# LED_Controller_Board.net
KiCad netlist of a schematic drawn in EAGLE
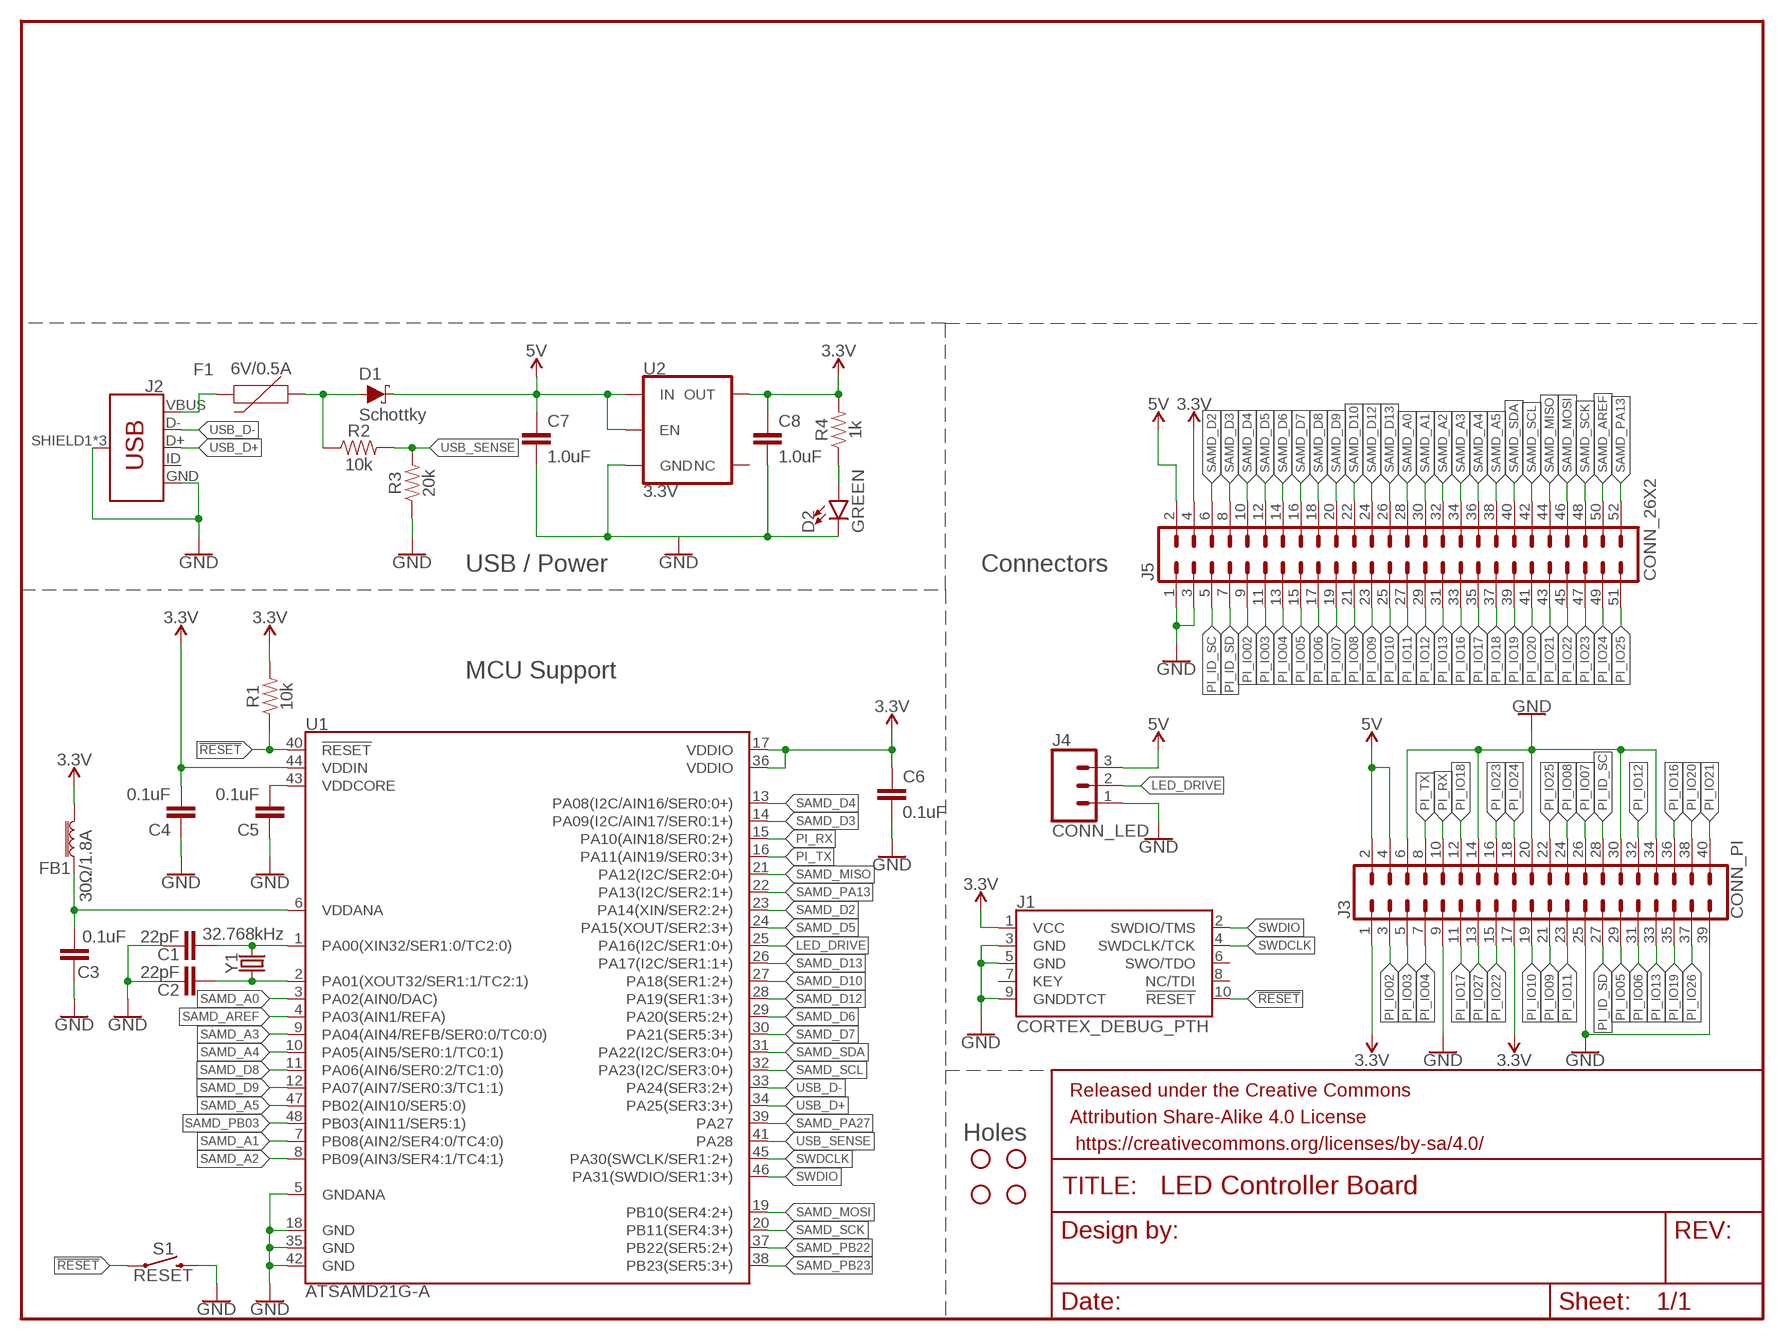
[diagram p0: schematic, sheet 1]

(export (version "E")
  (design (tool "Eeschema 10.0.6"))
  (components
    (comp (ref "C1")
      (value "22pF")
      (footprint "eagle-import:0603")
      (libsource (lib "eagle-import") (part "22PF-0603-50V-5%"))
    )
    (comp (ref "C2")
      (value "22pF")
      (footprint "eagle-import:0603")
      (libsource (lib "eagle-import") (part "22PF-0603-50V-5%"))
    )
    (comp (ref "C3")
      (value "0.1uF")
      (footprint "eagle-import:0603")
      (libsource (lib "eagle-import") (part "0.1UF-0603-25V-5%"))
    )
    (comp (ref "C4")
      (value "0.1uF")
      (footprint "eagle-import:0603")
      (libsource (lib "eagle-import") (part "0.1UF-0603-25V-5%"))
    )
    (comp (ref "C5")
      (value "0.1uF")
      (footprint "eagle-import:0603")
      (libsource (lib "eagle-import") (part "0.1UF-0603-25V-5%"))
    )
    (comp (ref "C6")
      (value "0.1uF")
      (footprint "eagle-import:0603")
      (libsource (lib "eagle-import") (part "0.1UF-0603-25V-5%"))
    )
    (comp (ref "C7")
      (value "1.0uF")
      (footprint "eagle-import:0603")
      (libsource (lib "eagle-import") (part "1.0UF-0603-16V-10%"))
    )
    (comp (ref "C8")
      (value "1.0uF")
      (footprint "eagle-import:0603")
      (libsource (lib "eagle-import") (part "1.0UF-0603-16V-10%"))
    )
    (comp (ref "D1")
      (value "Schottky")
      (footprint "eagle-import:SOD-323")
      (libsource (lib "eagle-import") (part "DIODE-SCHOTTKY-BAT20J"))
    )
    (comp (ref "D2")
      (value "GREEN")
      (footprint "eagle-import:LED-0603")
      (libsource (lib "eagle-import") (part "LED-GREEN0603"))
    )
    (comp (ref "F1")
      (value "6V/0.5A")
      (footprint "eagle-import:1206")
      (libsource (lib "eagle-import") (part "PPTC_HALF-AMP"))
    )
    (comp (ref "FB1")
      (value "30Ω/1.8A")
      (footprint "eagle-import:0603")
      (libsource (lib "eagle-import") (part "FERRITE_BEAD-0603"))
    )
    (comp (ref "FRAME1")
      (value "FRAME-LETTERNO_PACKAGE")
      (footprint "eagle-import:DUMMY")
      (fields (field (name "DESIGNER") "Nobody"))
      (libsource (lib "eagle-import") (part "FRAME-LETTERNO_PACKAGE"))
    )
    (comp (ref "H1")
      (value "STAND-OFFTIGHT")
      (footprint "eagle-import:STAND-OFF-TIGHT")
      (libsource (lib "eagle-import") (part "STAND-OFFTIGHT"))
    )
    (comp (ref "H2")
      (value "STAND-OFFTIGHT")
      (footprint "eagle-import:STAND-OFF-TIGHT")
      (libsource (lib "eagle-import") (part "STAND-OFFTIGHT"))
    )
    (comp (ref "H3")
      (value "STAND-OFFTIGHT")
      (footprint "eagle-import:STAND-OFF-TIGHT")
      (libsource (lib "eagle-import") (part "STAND-OFFTIGHT"))
    )
    (comp (ref "H4")
      (value "STAND-OFFTIGHT")
      (footprint "eagle-import:STAND-OFF-TIGHT")
      (libsource (lib "eagle-import") (part "STAND-OFFTIGHT"))
    )
    (comp (ref "J1")
      (value "CORTEX_DEBUG_PTH")
      (footprint "eagle-import:2X5-PTH-1.27MM")
      (libsource (lib "eagle-import") (part "CORTEX_DEBUG_PTH"))
    )
    (comp (ref "J2")
      (value "USB_MICRO-B_FEMALE-SMT")
      (footprint "eagle-import:USB-B-MICRO-SMD")
      (libsource (lib "eagle-import") (part "USB_MICRO-B_FEMALE-SMT"))
    )
    (comp (ref "J3")
      (value "CONN_PI")
      (footprint "eagle-import:2X20")
      (libsource (lib "eagle-import") (part "CONN_20X2"))
    )
    (comp (ref "J4")
      (value "CONN_LED")
      (footprint "eagle-import:1X03_LOCK")
      (libsource (lib "eagle-import") (part "CONN_03LOCK"))
    )
    (comp (ref "J5")
      (value "CONN_26X2")
      (footprint "eagle-import:2X26")
      (libsource (lib "eagle-import") (part "CONN_26X2"))
    )
    (comp (ref "R1")
      (value "10k")
      (footprint "eagle-import:0603")
      (libsource (lib "eagle-import") (part "10KOHM-0603-1/10W-1%"))
    )
    (comp (ref "R2")
      (value "10k")
      (footprint "eagle-import:0603")
      (libsource (lib "eagle-import") (part "10KOHM-0603-1/10W-1%"))
    )
    (comp (ref "R3")
      (value "20k")
      (footprint "eagle-import:0603")
      (libsource (lib "eagle-import") (part "20KOHM-0603-1/10W-1%"))
    )
    (comp (ref "R4")
      (value "1k")
      (footprint "eagle-import:0603")
      (libsource (lib "eagle-import") (part "1KOHM-0603-1/10W-1%"))
    )
    (comp (ref "S1")
      (value "RESET")
      (footprint "eagle-import:TACTILE_SWITCH_PTH_RIGHT_ANGLE_KIT")
      (libsource (lib "eagle-import") (part "MOMENTARY-SWITCH-SPST-PTH-RIGHT-ANGLE-KIT"))
    )
    (comp (ref "U1")
      (value "ATSAMD21G-A")
      (footprint "eagle-import:TQFP-48")
      (libsource (lib "eagle-import") (part "ATSAMD21G-A"))
    )
    (comp (ref "U2")
      (value "3.3V")
      (footprint "eagle-import:SOT23-5")
      (libsource (lib "eagle-import") (part "V_REG_AP2112K-3.3V"))
    )
    (comp (ref "Y1")
      (value "32.768kHz")
      (footprint "eagle-import:CRYSTAL-SMD-3.2X1.5MM")
      (libsource (lib "eagle-import") (part "CRYSTAL-32.768KHZSMD-3.2X1.5"))
    )
  )
  (nets
    (net (code "1") (name "/~{RESET}") (class "Default")
      (node (ref "J1") (pin "10") (pinfunction "~{RESET}_10") (pintype "bidirectional"))
      (node (ref "R1") (pin "1") (pinfunction "1_1") (pintype "passive"))
      (node (ref "S1") (pin "1") (pinfunction "1_1") (pintype "passive"))
      (node (ref "U1") (pin "40") (pinfunction "~{RESET}_40") (pintype "bidirectional"))
    )
    (net (code "2") (name "3.3V") (class "Default")
      (node (ref "C4") (pin "2") (pinfunction "2_2") (pintype "passive"))
      (node (ref "C6") (pin "1") (pinfunction "1_1") (pintype "passive"))
      (node (ref "C8") (pin "1") (pinfunction "1_1") (pintype "passive"))
      (node (ref "FB1") (pin "2") (pinfunction "2_2") (pintype "passive"))
      (node (ref "J1") (pin "1") (pinfunction "VCC_1") (pintype "bidirectional"))
      (node (ref "J3") (pin "1") (pinfunction "1_1") (pintype "passive"))
      (node (ref "J3") (pin "17") (pinfunction "17_17") (pintype "passive"))
      (node (ref "J5") (pin "4") (pinfunction "4_4") (pintype "passive"))
      (node (ref "R1") (pin "2") (pinfunction "2_2") (pintype "passive"))
      (node (ref "R4") (pin "2") (pinfunction "2_2") (pintype "passive"))
      (node (ref "U1") (pin "17") (pinfunction "VDDIO_17") (pintype "bidirectional"))
      (node (ref "U1") (pin "36") (pinfunction "VDDIO_36") (pintype "bidirectional"))
      (node (ref "U1") (pin "44") (pinfunction "VDDIN_44") (pintype "bidirectional"))
      (node (ref "U2") (pin "5") (pinfunction "OUT_5") (pintype "passive"))
    )
    (net (code "3") (name "5V") (class "Default")
      (node (ref "C7") (pin "1") (pinfunction "1_1") (pintype "passive"))
      (node (ref "D1") (pin "C") (pinfunction "C_C") (pintype "passive"))
      (node (ref "J3") (pin "2") (pinfunction "2_2") (pintype "passive"))
      (node (ref "J3") (pin "4") (pinfunction "4_4") (pintype "passive"))
      (node (ref "J4") (pin "3") (pinfunction "3_3") (pintype "passive"))
      (node (ref "J5") (pin "2") (pinfunction "2_2") (pintype "passive"))
      (node (ref "U2") (pin "1") (pinfunction "IN_1") (pintype "input"))
      (node (ref "U2") (pin "3") (pinfunction "EN_3") (pintype "input"))
    )
    (net (code "4") (name "GND") (class "Default")
      (node (ref "C1") (pin "1") (pinfunction "1_1") (pintype "passive"))
      (node (ref "C2") (pin "1") (pinfunction "1_1") (pintype "passive"))
      (node (ref "C3") (pin "1") (pinfunction "1_1") (pintype "passive"))
      (node (ref "C4") (pin "1") (pinfunction "1_1") (pintype "passive"))
      (node (ref "C5") (pin "1") (pinfunction "1_1") (pintype "passive"))
      (node (ref "C6") (pin "2") (pinfunction "2_2") (pintype "passive"))
      (node (ref "C7") (pin "2") (pinfunction "2_2") (pintype "passive"))
      (node (ref "C8") (pin "2") (pinfunction "2_2") (pintype "passive"))
      (node (ref "D2") (pin "C") (pinfunction "C_C") (pintype "passive"))
      (node (ref "J1") (pin "3") (pinfunction "GND_3") (pintype "bidirectional"))
      (node (ref "J1") (pin "5") (pinfunction "GND_5") (pintype "bidirectional"))
      (node (ref "J1") (pin "9") (pinfunction "GNDDTCT_9") (pintype "bidirectional"))
      (node (ref "J2") (pin "GND") (pinfunction "GND_GND") (pintype "power_in"))
      (node (ref "J2") (pin "SHIELD1") (pinfunction "SHIELD_SHIELD1") (pintype "bidirectional"))
      (node (ref "J2") (pin "SHIELD2") (pinfunction "SHIELD_SHIELD2") (pintype "bidirectional"))
      (node (ref "J2") (pin "SHIELD3") (pinfunction "SHIELD_SHIELD3") (pintype "bidirectional"))
      (node (ref "J3") (pin "14") (pinfunction "14_14") (pintype "passive"))
      (node (ref "J3") (pin "20") (pinfunction "20_20") (pintype "passive"))
      (node (ref "J3") (pin "25") (pinfunction "25_25") (pintype "passive"))
      (node (ref "J3") (pin "30") (pinfunction "30_30") (pintype "passive"))
      (node (ref "J3") (pin "34") (pinfunction "34_34") (pintype "passive"))
      (node (ref "J3") (pin "39") (pinfunction "39_39") (pintype "passive"))
      (node (ref "J3") (pin "6") (pinfunction "6_6") (pintype "passive"))
      (node (ref "J3") (pin "9") (pinfunction "9_9") (pintype "passive"))
      (node (ref "J4") (pin "1") (pinfunction "1_1") (pintype "passive"))
      (node (ref "J5") (pin "1") (pinfunction "1_1") (pintype "passive"))
      (node (ref "J5") (pin "3") (pinfunction "3_3") (pintype "passive"))
      (node (ref "R3") (pin "1") (pinfunction "1_1") (pintype "passive"))
      (node (ref "S1") (pin "2") (pinfunction "2_2") (pintype "passive"))
      (node (ref "U1") (pin "18") (pinfunction "GND_18") (pintype "bidirectional"))
      (node (ref "U1") (pin "35") (pinfunction "GND_35") (pintype "bidirectional"))
      (node (ref "U1") (pin "42") (pinfunction "GND_42") (pintype "bidirectional"))
      (node (ref "U1") (pin "5") (pinfunction "GNDANA_5") (pintype "bidirectional"))
      (node (ref "U2") (pin "2") (pinfunction "GND_2") (pintype "input"))
    )
    (net (code "5") (name "LED_DRIVE") (class "Default")
      (node (ref "J4") (pin "2") (pinfunction "2_2") (pintype "passive"))
      (node (ref "U1") (pin "25") (pinfunction "PA16(I2C/SER1:0+)_25") (pintype "bidirectional"))
    )
    (net (code "6") (name "Net-(D1-PadA)") (class "Default")
      (node (ref "D1") (pin "A") (pinfunction "A_A") (pintype "passive"))
      (node (ref "F1") (pin "1") (pinfunction "1_1") (pintype "bidirectional"))
      (node (ref "R2") (pin "1") (pinfunction "1_1") (pintype "passive"))
    )
    (net (code "7") (name "Net-(D2-PadA)") (class "Default")
      (node (ref "D2") (pin "A") (pinfunction "A_A") (pintype "passive"))
      (node (ref "R4") (pin "1") (pinfunction "1_1") (pintype "passive"))
    )
    (net (code "8") (name "Net-(F1-Pad2)") (class "Default")
      (node (ref "F1") (pin "2") (pinfunction "2_2") (pintype "bidirectional"))
      (node (ref "J2") (pin "VBUS") (pinfunction "VBUS_VBUS") (pintype "power_in"))
    )
    (net (code "9") (name "Net-(U1-PA00(XIN32{slash}SER1:0{slash}TC2:0))") (class "Default")
      (node (ref "C1") (pin "2") (pinfunction "2_2") (pintype "passive"))
      (node (ref "U1") (pin "1") (pinfunction "PA00(XIN32/SER1:0/TC2:0)_1") (pintype "bidirectional"))
      (node (ref "Y1") (pin "P$2") (pinfunction "2_P$2") (pintype "passive"))
    )
    (net (code "10") (name "Net-(U1-PA01(XOUT32{slash}SER1:1{slash}TC2:1))") (class "Default")
      (node (ref "C2") (pin "2") (pinfunction "2_2") (pintype "passive"))
      (node (ref "U1") (pin "2") (pinfunction "PA01(XOUT32/SER1:1/TC2:1)_2") (pintype "bidirectional"))
      (node (ref "Y1") (pin "P$1") (pinfunction "1_P$1") (pintype "passive"))
    )
    (net (code "11") (name "Net-(U1-VDDANA)") (class "Default")
      (node (ref "C3") (pin "2") (pinfunction "2_2") (pintype "passive"))
      (node (ref "FB1") (pin "1") (pinfunction "1_1") (pintype "passive"))
      (node (ref "U1") (pin "6") (pinfunction "VDDANA_6") (pintype "bidirectional"))
    )
    (net (code "12") (name "Net-(U1-VDDCORE)") (class "Default")
      (node (ref "C5") (pin "2") (pinfunction "2_2") (pintype "passive"))
      (node (ref "U1") (pin "43") (pinfunction "VDDCORE_43") (pintype "bidirectional"))
    )
    (net (code "13") (name "PI_ID_SC") (class "Default")
      (node (ref "J3") (pin "28") (pinfunction "28_28") (pintype "passive"))
      (node (ref "J5") (pin "5") (pinfunction "5_5") (pintype "passive"))
    )
    (net (code "14") (name "PI_ID_SD") (class "Default")
      (node (ref "J3") (pin "27") (pinfunction "27_27") (pintype "passive"))
      (node (ref "J5") (pin "7") (pinfunction "7_7") (pintype "passive"))
    )
    (net (code "15") (name "PI_IO02") (class "Default")
      (node (ref "J3") (pin "3") (pinfunction "3_3") (pintype "passive"))
      (node (ref "J5") (pin "9") (pinfunction "9_9") (pintype "passive"))
    )
    (net (code "16") (name "PI_IO03") (class "Default")
      (node (ref "J3") (pin "5") (pinfunction "5_5") (pintype "passive"))
      (node (ref "J5") (pin "11") (pinfunction "11_11") (pintype "passive"))
    )
    (net (code "17") (name "PI_IO04") (class "Default")
      (node (ref "J3") (pin "7") (pinfunction "7_7") (pintype "passive"))
      (node (ref "J5") (pin "13") (pinfunction "13_13") (pintype "passive"))
    )
    (net (code "18") (name "PI_IO05") (class "Default")
      (node (ref "J3") (pin "29") (pinfunction "29_29") (pintype "passive"))
      (node (ref "J5") (pin "15") (pinfunction "15_15") (pintype "passive"))
    )
    (net (code "19") (name "PI_IO06") (class "Default")
      (node (ref "J3") (pin "31") (pinfunction "31_31") (pintype "passive"))
      (node (ref "J5") (pin "17") (pinfunction "17_17") (pintype "passive"))
    )
    (net (code "20") (name "PI_IO07") (class "Default")
      (node (ref "J3") (pin "26") (pinfunction "26_26") (pintype "passive"))
      (node (ref "J5") (pin "19") (pinfunction "19_19") (pintype "passive"))
    )
    (net (code "21") (name "PI_IO08") (class "Default")
      (node (ref "J3") (pin "24") (pinfunction "24_24") (pintype "passive"))
      (node (ref "J5") (pin "21") (pinfunction "21_21") (pintype "passive"))
    )
    (net (code "22") (name "PI_IO09") (class "Default")
      (node (ref "J3") (pin "21") (pinfunction "21_21") (pintype "passive"))
      (node (ref "J5") (pin "23") (pinfunction "23_23") (pintype "passive"))
    )
    (net (code "23") (name "PI_IO10") (class "Default")
      (node (ref "J3") (pin "19") (pinfunction "19_19") (pintype "passive"))
      (node (ref "J5") (pin "25") (pinfunction "25_25") (pintype "passive"))
    )
    (net (code "24") (name "PI_IO11") (class "Default")
      (node (ref "J3") (pin "23") (pinfunction "23_23") (pintype "passive"))
      (node (ref "J5") (pin "27") (pinfunction "27_27") (pintype "passive"))
    )
    (net (code "25") (name "PI_IO12") (class "Default")
      (node (ref "J3") (pin "32") (pinfunction "32_32") (pintype "passive"))
      (node (ref "J5") (pin "29") (pinfunction "29_29") (pintype "passive"))
    )
    (net (code "26") (name "PI_IO13") (class "Default")
      (node (ref "J3") (pin "33") (pinfunction "33_33") (pintype "passive"))
      (node (ref "J5") (pin "31") (pinfunction "31_31") (pintype "passive"))
    )
    (net (code "27") (name "PI_IO16") (class "Default")
      (node (ref "J3") (pin "36") (pinfunction "36_36") (pintype "passive"))
      (node (ref "J5") (pin "33") (pinfunction "33_33") (pintype "passive"))
    )
    (net (code "28") (name "PI_IO17") (class "Default")
      (node (ref "J3") (pin "11") (pinfunction "11_11") (pintype "passive"))
      (node (ref "J5") (pin "35") (pinfunction "35_35") (pintype "passive"))
    )
    (net (code "29") (name "PI_IO18") (class "Default")
      (node (ref "J3") (pin "12") (pinfunction "12_12") (pintype "passive"))
      (node (ref "J5") (pin "37") (pinfunction "37_37") (pintype "passive"))
    )
    (net (code "30") (name "PI_IO19") (class "Default")
      (node (ref "J3") (pin "35") (pinfunction "35_35") (pintype "passive"))
      (node (ref "J5") (pin "39") (pinfunction "39_39") (pintype "passive"))
    )
    (net (code "31") (name "PI_IO20") (class "Default")
      (node (ref "J3") (pin "38") (pinfunction "38_38") (pintype "passive"))
      (node (ref "J5") (pin "41") (pinfunction "41_41") (pintype "passive"))
    )
    (net (code "32") (name "PI_IO21") (class "Default")
      (node (ref "J3") (pin "40") (pinfunction "40_40") (pintype "passive"))
      (node (ref "J5") (pin "43") (pinfunction "43_43") (pintype "passive"))
    )
    (net (code "33") (name "PI_IO22") (class "Default")
      (node (ref "J3") (pin "15") (pinfunction "15_15") (pintype "passive"))
      (node (ref "J5") (pin "45") (pinfunction "45_45") (pintype "passive"))
    )
    (net (code "34") (name "PI_IO23") (class "Default")
      (node (ref "J3") (pin "16") (pinfunction "16_16") (pintype "passive"))
      (node (ref "J5") (pin "47") (pinfunction "47_47") (pintype "passive"))
    )
    (net (code "35") (name "PI_IO24") (class "Default")
      (node (ref "J3") (pin "18") (pinfunction "18_18") (pintype "passive"))
      (node (ref "J5") (pin "49") (pinfunction "49_49") (pintype "passive"))
    )
    (net (code "36") (name "PI_IO25") (class "Default")
      (node (ref "J3") (pin "22") (pinfunction "22_22") (pintype "passive"))
      (node (ref "J5") (pin "51") (pinfunction "51_51") (pintype "passive"))
    )
    (net (code "37") (name "PI_IO26") (class "Default")
      (node (ref "J3") (pin "37") (pinfunction "37_37") (pintype "passive"))
    )
    (net (code "38") (name "PI_IO27") (class "Default")
      (node (ref "J3") (pin "13") (pinfunction "13_13") (pintype "passive"))
    )
    (net (code "39") (name "PI_RX") (class "Default")
      (node (ref "J3") (pin "10") (pinfunction "10_10") (pintype "passive"))
      (node (ref "U1") (pin "15") (pinfunction "PA10(AIN18/SER0:2+)_15") (pintype "bidirectional"))
    )
    (net (code "40") (name "PI_TX") (class "Default")
      (node (ref "J3") (pin "8") (pinfunction "8_8") (pintype "passive"))
      (node (ref "U1") (pin "16") (pinfunction "PA11(AIN19/SER0:3+)_16") (pintype "bidirectional"))
    )
    (net (code "41") (name "SAMD_A0") (class "Default")
      (node (ref "J5") (pin "28") (pinfunction "28_28") (pintype "passive"))
      (node (ref "U1") (pin "3") (pinfunction "PA02(AIN0/DAC)_3") (pintype "bidirectional"))
    )
    (net (code "42") (name "SAMD_A1") (class "Default")
      (node (ref "J5") (pin "30") (pinfunction "30_30") (pintype "passive"))
      (node (ref "U1") (pin "7") (pinfunction "PB08(AIN2/SER4:0/TC4:0)_7") (pintype "bidirectional"))
    )
    (net (code "43") (name "SAMD_A2") (class "Default")
      (node (ref "J5") (pin "32") (pinfunction "32_32") (pintype "passive"))
      (node (ref "U1") (pin "8") (pinfunction "PB09(AIN3/SER4:1/TC4:1)_8") (pintype "bidirectional"))
    )
    (net (code "44") (name "SAMD_A3") (class "Default")
      (node (ref "J5") (pin "34") (pinfunction "34_34") (pintype "passive"))
      (node (ref "U1") (pin "9") (pinfunction "PA04(AIN4/REFB/SER0:0/TC0:0)_9") (pintype "bidirectional"))
    )
    (net (code "45") (name "SAMD_A4") (class "Default")
      (node (ref "J5") (pin "36") (pinfunction "36_36") (pintype "passive"))
      (node (ref "U1") (pin "10") (pinfunction "PA05(AIN5/SER0:1/TC0:1)_10") (pintype "bidirectional"))
    )
    (net (code "46") (name "SAMD_A5") (class "Default")
      (node (ref "J5") (pin "38") (pinfunction "38_38") (pintype "passive"))
      (node (ref "U1") (pin "47") (pinfunction "PB02(AIN10/SER5:0)_47") (pintype "bidirectional"))
    )
    (net (code "47") (name "SAMD_AREF") (class "Default")
      (node (ref "J5") (pin "50") (pinfunction "50_50") (pintype "passive"))
      (node (ref "U1") (pin "4") (pinfunction "PA03(AIN1/REFA)_4") (pintype "bidirectional"))
    )
    (net (code "48") (name "SAMD_D2") (class "Default")
      (node (ref "J5") (pin "6") (pinfunction "6_6") (pintype "passive"))
      (node (ref "U1") (pin "23") (pinfunction "PA14(XIN/SER2:2+)_23") (pintype "bidirectional"))
    )
    (net (code "49") (name "SAMD_D3") (class "Default")
      (node (ref "J5") (pin "8") (pinfunction "8_8") (pintype "passive"))
      (node (ref "U1") (pin "14") (pinfunction "PA09(I2C/AIN17/SER0:1+)_14") (pintype "bidirectional"))
    )
    (net (code "50") (name "SAMD_D4") (class "Default")
      (node (ref "J5") (pin "10") (pinfunction "10_10") (pintype "passive"))
      (node (ref "U1") (pin "13") (pinfunction "PA08(I2C/AIN16/SER0:0+)_13") (pintype "bidirectional"))
    )
    (net (code "51") (name "SAMD_D5") (class "Default")
      (node (ref "J5") (pin "12") (pinfunction "12_12") (pintype "passive"))
      (node (ref "U1") (pin "24") (pinfunction "PA15(XOUT/SER2:3+)_24") (pintype "bidirectional"))
    )
    (net (code "52") (name "SAMD_D6") (class "Default")
      (node (ref "J5") (pin "14") (pinfunction "14_14") (pintype "passive"))
      (node (ref "U1") (pin "29") (pinfunction "PA20(SER5:2+)_29") (pintype "bidirectional"))
    )
    (net (code "53") (name "SAMD_D7") (class "Default")
      (node (ref "J5") (pin "16") (pinfunction "16_16") (pintype "passive"))
      (node (ref "U1") (pin "30") (pinfunction "PA21(SER5:3+)_30") (pintype "bidirectional"))
    )
    (net (code "54") (name "SAMD_D8") (class "Default")
      (node (ref "J5") (pin "18") (pinfunction "18_18") (pintype "passive"))
      (node (ref "U1") (pin "11") (pinfunction "PA06(AIN6/SER0:2/TC1:0)_11") (pintype "bidirectional"))
    )
    (net (code "55") (name "SAMD_D9") (class "Default")
      (node (ref "J5") (pin "20") (pinfunction "20_20") (pintype "passive"))
      (node (ref "U1") (pin "12") (pinfunction "PA07(AIN7/SER0:3/TC1:1)_12") (pintype "bidirectional"))
    )
    (net (code "56") (name "SAMD_D10") (class "Default")
      (node (ref "J5") (pin "22") (pinfunction "22_22") (pintype "passive"))
      (node (ref "U1") (pin "27") (pinfunction "PA18(SER1:2+)_27") (pintype "bidirectional"))
    )
    (net (code "57") (name "SAMD_D12") (class "Default")
      (node (ref "J5") (pin "24") (pinfunction "24_24") (pintype "passive"))
      (node (ref "U1") (pin "28") (pinfunction "PA19(SER1:3+)_28") (pintype "bidirectional"))
    )
    (net (code "58") (name "SAMD_D13") (class "Default")
      (node (ref "J5") (pin "26") (pinfunction "26_26") (pintype "passive"))
      (node (ref "U1") (pin "26") (pinfunction "PA17(I2C/SER1:1+)_26") (pintype "bidirectional"))
    )
    (net (code "59") (name "SAMD_MISO") (class "Default")
      (node (ref "J5") (pin "44") (pinfunction "44_44") (pintype "passive"))
      (node (ref "U1") (pin "21") (pinfunction "PA12(I2C/SER2:0+)_21") (pintype "bidirectional"))
    )
    (net (code "60") (name "SAMD_MOSI") (class "Default")
      (node (ref "J5") (pin "46") (pinfunction "46_46") (pintype "passive"))
      (node (ref "U1") (pin "19") (pinfunction "PB10(SER4:2+)_19") (pintype "bidirectional"))
    )
    (net (code "61") (name "SAMD_PA13") (class "Default")
      (node (ref "J5") (pin "52") (pinfunction "52_52") (pintype "passive"))
      (node (ref "U1") (pin "22") (pinfunction "PA13(I2C/SER2:1+)_22") (pintype "bidirectional"))
    )
    (net (code "62") (name "SAMD_PA27") (class "Default")
      (node (ref "U1") (pin "39") (pinfunction "PA27_39") (pintype "bidirectional"))
    )
    (net (code "63") (name "SAMD_PB03") (class "Default")
      (node (ref "U1") (pin "48") (pinfunction "PB03(AIN11/SER5:1)_48") (pintype "bidirectional"))
    )
    (net (code "64") (name "SAMD_PB22") (class "Default")
      (node (ref "U1") (pin "37") (pinfunction "PB22(SER5:2+)_37") (pintype "bidirectional"))
    )
    (net (code "65") (name "SAMD_PB23") (class "Default")
      (node (ref "U1") (pin "38") (pinfunction "PB23(SER5:3+)_38") (pintype "bidirectional"))
    )
    (net (code "66") (name "SAMD_SCK") (class "Default")
      (node (ref "J5") (pin "48") (pinfunction "48_48") (pintype "passive"))
      (node (ref "U1") (pin "20") (pinfunction "PB11(SER4:3+)_20") (pintype "bidirectional"))
    )
    (net (code "67") (name "SAMD_SCL") (class "Default")
      (node (ref "J5") (pin "42") (pinfunction "42_42") (pintype "passive"))
      (node (ref "U1") (pin "32") (pinfunction "PA23(I2C/SER3:0+)_32") (pintype "bidirectional"))
    )
    (net (code "68") (name "SAMD_SDA") (class "Default")
      (node (ref "J5") (pin "40") (pinfunction "40_40") (pintype "passive"))
      (node (ref "U1") (pin "31") (pinfunction "PA22(I2C/SER3:0+)_31") (pintype "bidirectional"))
    )
    (net (code "69") (name "SWDCLK") (class "Default")
      (node (ref "J1") (pin "4") (pinfunction "SWDCLK/TCK_4") (pintype "bidirectional"))
      (node (ref "U1") (pin "45") (pinfunction "PA30(SWCLK/SER1:2+)_45") (pintype "bidirectional"))
    )
    (net (code "70") (name "SWDIO") (class "Default")
      (node (ref "J1") (pin "2") (pinfunction "SWDIO/TMS_2") (pintype "bidirectional"))
      (node (ref "U1") (pin "46") (pinfunction "PA31(SWDIO/SER1:3+)_46") (pintype "bidirectional"))
    )
    (net (code "71") (name "USB_D+") (class "Default")
      (node (ref "J2") (pin "D+") (pinfunction "D+_D+") (pintype "bidirectional"))
      (node (ref "U1") (pin "34") (pinfunction "PA25(SER3:3+)_34") (pintype "bidirectional"))
    )
    (net (code "72") (name "USB_D-") (class "Default")
      (node (ref "J2") (pin "D-") (pinfunction "D-_D-") (pintype "bidirectional"))
      (node (ref "U1") (pin "33") (pinfunction "PA24(SER3:2+)_33") (pintype "bidirectional"))
    )
    (net (code "73") (name "USB_SENSE") (class "Default")
      (node (ref "R2") (pin "2") (pinfunction "2_2") (pintype "passive"))
      (node (ref "R3") (pin "2") (pinfunction "2_2") (pintype "passive"))
      (node (ref "U1") (pin "41") (pinfunction "PA28_41") (pintype "bidirectional"))
    )
    (net (code "74") (name "unconnected-(J1-KEY-Pad7)") (class "Default")
      (node (ref "J1") (pin "7") (pinfunction "KEY_7") (pintype "bidirectional"))
    )
    (net (code "75") (name "unconnected-(J1-NC{slash}TDI-Pad8)") (class "Default")
      (node (ref "J1") (pin "8") (pinfunction "NC/TDI_8") (pintype "bidirectional"))
    )
    (net (code "76") (name "unconnected-(J1-SWO{slash}TDO-Pad6)") (class "Default")
      (node (ref "J1") (pin "6") (pinfunction "SWO/TDO_6") (pintype "bidirectional"))
    )
    (net (code "77") (name "unconnected-(J2-PadID)") (class "Default")
      (node (ref "J2") (pin "ID") (pinfunction "ID_ID") (pintype "bidirectional"))
    )
    (net (code "78") (name "unconnected-(U2-NC-Pad4)") (class "Default")
      (node (ref "U2") (pin "4") (pinfunction "NC_4") (pintype "no_connect"))
    )
  )
)
